# Power_Line_24V.net
KiCad netlist of a schematic drawn in Altium Designer
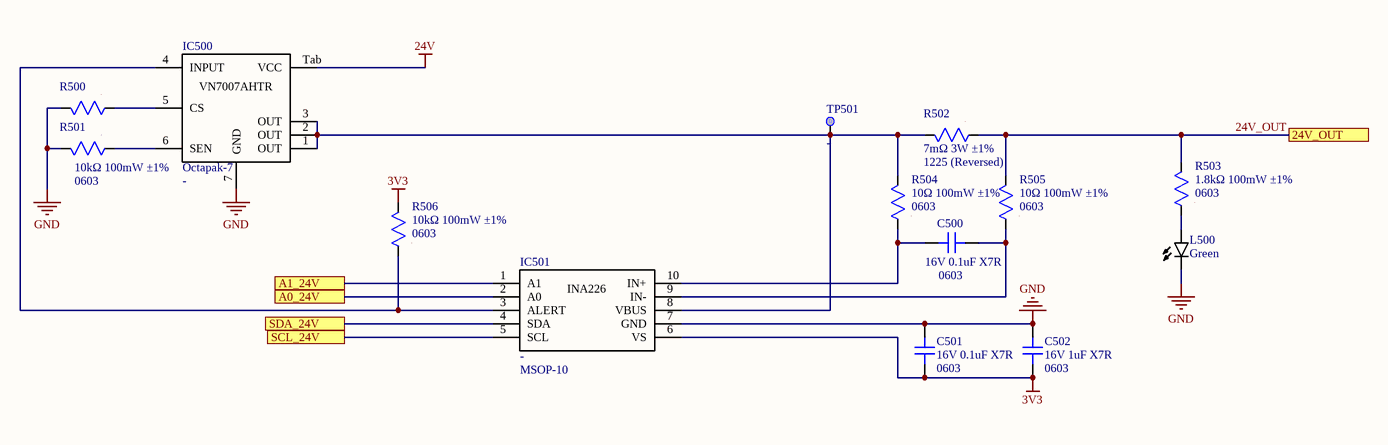
[diagram p0: Power_Line_24V.SchDoc]

(export (version "E")
  (design (tool "Eeschema 10.0.6"))
  (components
    (comp (ref "C500")
      (value "16V 0.1uF X7R")
      (footprint "CAP SMD 0603")
      (description "Condensadores de cerámica multicapa (MLCC- SMD/SMT) WCAP-CSGP 0.1uF 0603 10% 16V MLCC")
      (fields
        (field (name "PACKAGE") "0603")
        (field (name "MPN") "885012206046")
        (field (name "MANUFACTURER") "Wurth Elektronik")
      )
      (libsource (lib "eUSR_Database") (part "CAP non polarized"))
    )
    (comp (ref "C501")
      (value "16V 0.1uF X7R")
      (footprint "CAP SMD 0603")
      (description "Condensadores de cerámica multicapa (MLCC- SMD/SMT) WCAP-CSGP 0.1uF 0603 10% 16V MLCC")
      (fields
        (field (name "PACKAGE") "0603")
        (field (name "MPN") "885012206046")
        (field (name "MANUFACTURER") "Wurth Elektronik")
      )
      (libsource (lib "eUSR_Database") (part "CAP non polarized"))
    )
    (comp (ref "C502")
      (value "16V 1uF X7R")
      (footprint "CAP SMD 0603")
      (description "Condensadores de cerámica multicapa (MLCC- SMD/SMT) WCAP-CSGP 1uF 0603 10% 16V MLCC")
      (fields
        (field (name "PACKAGE") "0603")
        (field (name "MPN") "885012206052")
        (field (name "MANUFACTURER") "Wurth Elektronik")
      )
      (libsource (lib "eUSR_Database") (part "CAP non polarized"))
    )
    (comp (ref "IC500")
      (value "-")
      (footprint "Octapak-7")
      (fields
        (field (name "PACKAGE") "Octapak-7")
        (field (name "MPN") "VN7007AHTR")
        (field (name "MANUFACTURER") "511-VN7007AHTR")
      )
      (libsource (lib "eUSR_Database") (part "VN7007AHTR"))
    )
    (comp (ref "IC501")
      (value "-")
      (footprint "VSOP-10")
      (fields
        (field (name "PACKAGE") "MSOP-10")
        (field (name "MPN") "INA226AIDGSR")
        (field (name "MANUFACTURER") "595-INA226AIDGSR")
        (field (name "Comment") "INA226")
      )
      (libsource (lib "eUSR_Database") (part "INA226"))
    )
    (comp (ref "L500")
      (value "Green")
      (footprint "LED SMD 0603")
      (description "LED de un solo color Green 525nm 1400mcd 2.85V 73deg 0603")
      (fields (field (name "MPN") "VLMTG1400-GS08") (field (name "MANUFACTURER") "Vishay Semiconductors"))
      (libsource (lib "eUSR_Database") (part "LED WHITE"))
    )
    (comp (ref "R500")
      (value "RES")
      (footprint "RES SMD 0603")
      (description "Resistores de película gruesa - SMD WRIS-RSKS 10 kOhms 1 % 0.1 W 0603 AEC-Q200")
      (fields (field (name "MPN") "560112116005") (field (name "MANUFACTURER") "Wurth Elektronik"))
      (libsource (lib "eUSR_Database") (part "RES"))
    )
    (comp (ref "R501")
      (value "10kΩ 100mW ±1%")
      (footprint "RES SMD 0603")
      (description "Resistores de película gruesa - SMD WRIS-RSKS 10 kOhms 1 % 0.1 W 0603 AEC-Q200")
      (fields
        (field (name "PACKAGE") "0603")
        (field (name "MPN") "560112116005")
        (field (name "MANUFACTURER") "Wurth Elektronik")
      )
      (libsource (lib "eUSR_Database") (part "RES"))
    )
    (comp (ref "R502")
      (value "7mΩ 3W ±1%")
      (footprint "RES SMD 1225 Reversed")
      (description "Resistores de detección de corriente - SMD 3W 0.007ohm 1% 50ppm")
      (fields
        (field (name "PACKAGE") "1225 (Reversed)")
        (field (name "MPN") "KRL6432E-M-R007-F-T1")
        (field (name "MANUFACTURER") "Susumu")
      )
      (libsource (lib "eUSR_Database") (part "RES"))
    )
    (comp (ref "R503")
      (value "1.8kΩ 100mW ±1%")
      (footprint "RES SMD 0603")
      (description "Resistores de película gruesa - SMD WRIS-RSKS 1.8 kOhms 1 % 0.1 W 0603 AEC-Q200")
      (fields
        (field (name "PACKAGE") "0603")
        (field (name "MPN") "560112116032")
        (field (name "MANUFACTURER") "Wurth Elektronik")
      )
      (libsource (lib "eUSR_Database") (part "RES"))
    )
    (comp (ref "R504")
      (value "10Ω 100mW ±1%")
      (footprint "RES SMD 0603")
      (description "Resistores de película gruesa - SMD WRIS-RSKS 10 Ohms 1 % 0.1 W 0603 AEC-Q200")
      (fields
        (field (name "PACKAGE") "0603")
        (field (name "MPN") "560112116013")
        (field (name "MANUFACTURER") "Wurth Elektronik")
      )
      (libsource (lib "eUSR_Database") (part "RES"))
    )
    (comp (ref "R505")
      (value "10Ω 100mW ±1%")
      (footprint "RES SMD 0603")
      (description "Resistores de película gruesa - SMD WRIS-RSKS 10 Ohms 1 % 0.1 W 0603 AEC-Q200")
      (fields
        (field (name "PACKAGE") "0603")
        (field (name "MPN") "560112116013")
        (field (name "MANUFACTURER") "Wurth Elektronik")
      )
      (libsource (lib "eUSR_Database") (part "RES"))
    )
    (comp (ref "R506")
      (value "10kΩ 100mW ±1%")
      (footprint "RES SMD 0603")
      (description "Resistores de película gruesa - SMD WRIS-RSKS 10 kOhms 1 % 0.1 W 0603 AEC-Q200")
      (fields
        (field (name "PACKAGE") "0603")
        (field (name "MPN") "560112116005")
        (field (name "MANUFACTURER") "Wurth Elektronik")
      )
      (libsource (lib "eUSR_Database") (part "RES"))
    )
    (comp (ref "TP501")
      (value "-")
      (footprint "TP_SMD_1MM")
      (description "Test Point")
      (libsource (lib "eUSR_Database") (part "TP1mm"))
    )
  )
  (nets
    (net (code "1") (name "/24V_OUT") (class "Default")
      (node (ref "R502") (pin "1") (pinfunction "1_1") (pintype "passive"))
      (node (ref "R503") (pin "2") (pinfunction "2_2") (pintype "passive"))
      (node (ref "R505") (pin "2") (pinfunction "2_2") (pintype "passive"))
    )
    (net (code "2") (name "/A0_24V") (class "Default")
      (node (ref "IC501") (pin "2") (pinfunction "A0_2") (pintype "passive"))
    )
    (net (code "3") (name "/A1_24V") (class "Default")
      (node (ref "IC501") (pin "1") (pinfunction "A1_1") (pintype "passive"))
    )
    (net (code "4") (name "/SCL_24V") (class "Default")
      (node (ref "IC501") (pin "5") (pinfunction "SCL_5") (pintype "passive"))
    )
    (net (code "5") (name "/SDA_24V") (class "Default")
      (node (ref "IC501") (pin "4") (pinfunction "SDA_4") (pintype "passive"))
    )
    (net (code "6") (name "3V3") (class "Default")
      (node (ref "C501") (pin "2") (pinfunction "2_2") (pintype "passive"))
      (node (ref "C502") (pin "2") (pinfunction "2_2") (pintype "passive"))
      (node (ref "IC501") (pin "6") (pinfunction "VS_6") (pintype "passive"))
      (node (ref "R506") (pin "2") (pinfunction "2_2") (pintype "passive"))
    )
    (net (code "7") (name "24V") (class "Default")
      (node (ref "IC500") (pin "Tab") (pinfunction "VCC_Tab") (pintype "passive"))
    )
    (net (code "8") (name "GND") (class "Default")
      (node (ref "C501") (pin "1") (pinfunction "1_1") (pintype "passive"))
      (node (ref "C502") (pin "1") (pinfunction "1_1") (pintype "passive"))
      (node (ref "IC500") (pin "7") (pinfunction "GND_7") (pintype "passive"))
      (node (ref "IC501") (pin "7") (pinfunction "GND_7") (pintype "passive"))
      (node (ref "L500") (pin "C") (pinfunction "C_C") (pintype "passive"))
      (node (ref "R500") (pin "2") (pinfunction "2_2") (pintype "passive"))
      (node (ref "R501") (pin "2") (pinfunction "2_2") (pintype "passive"))
    )
    (net (code "9") (name "Net-(IC500-CS)") (class "Default")
      (node (ref "IC500") (pin "5") (pinfunction "CS_5") (pintype "passive"))
      (node (ref "R500") (pin "1") (pinfunction "1_1") (pintype "passive"))
    )
    (net (code "10") (name "Net-(IC500-INPUT)") (class "Default")
      (node (ref "IC500") (pin "4") (pinfunction "INPUT_4") (pintype "passive"))
      (node (ref "IC501") (pin "3") (pinfunction "ALERT_3") (pintype "passive"))
      (node (ref "R506") (pin "1") (pinfunction "1_1") (pintype "passive"))
    )
    (net (code "11") (name "Net-(IC500-SEN)") (class "Default")
      (node (ref "IC500") (pin "6") (pinfunction "SEN_6") (pintype "passive"))
      (node (ref "R501") (pin "1") (pinfunction "1_1") (pintype "passive"))
    )
    (net (code "12") (name "Net-(IC501-IN+)") (class "Default")
      (node (ref "C500") (pin "1") (pinfunction "1_1") (pintype "passive"))
      (node (ref "IC501") (pin "10") (pinfunction "IN+_10") (pintype "passive"))
      (node (ref "R504") (pin "1") (pinfunction "1_1") (pintype "passive"))
    )
    (net (code "13") (name "Net-(IC501-IN-)") (class "Default")
      (node (ref "C500") (pin "2") (pinfunction "2_2") (pintype "passive"))
      (node (ref "IC501") (pin "9") (pinfunction "IN-_9") (pintype "passive"))
      (node (ref "R505") (pin "1") (pinfunction "1_1") (pintype "passive"))
    )
    (net (code "14") (name "Net-(IC501-VBUS)") (class "Default")
      (node (ref "IC500") (pin "1") (pinfunction "OUT_1") (pintype "passive"))
      (node (ref "IC500") (pin "2") (pinfunction "OUT_2") (pintype "passive"))
      (node (ref "IC500") (pin "3") (pinfunction "OUT_3") (pintype "passive"))
      (node (ref "IC501") (pin "8") (pinfunction "VBUS_8") (pintype "passive"))
      (node (ref "R502") (pin "2") (pinfunction "2_2") (pintype "passive"))
      (node (ref "R504") (pin "2") (pinfunction "2_2") (pintype "passive"))
      (node (ref "TP501") (pin "1") (pinfunction "1_1") (pintype "passive"))
    )
    (net (code "15") (name "Net-(L500-PadA)") (class "Default")
      (node (ref "L500") (pin "A") (pinfunction "A_A") (pintype "passive"))
      (node (ref "R503") (pin "1") (pinfunction "1_1") (pintype "passive"))
    )
  )
)
